# amp_ganho_ajustavel.net
KiCad netlist of a schematic drawn in Altium Designer
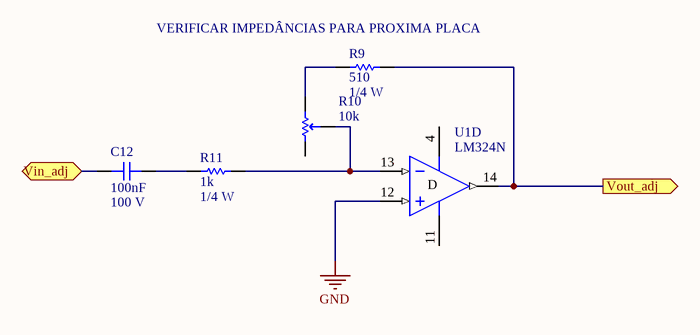
[diagram p0: amp_ganho_ajustavel.SchDoc]

(export (version "E")
  (design (tool "Eeschema 10.0.6"))
  (components
    (comp (ref "C12")
      (value "100nF")
      (footprint "0805C")
      (description "Capacitor")
      (fields (field (name "VOLTAGE") "100 V") (field (name "PUBLISHER") "Altium Limited"))
      (libsource (lib "GPDSE") (part "Capacitor"))
    )
    (comp (ref "R9")
      (value "510")
      (footprint "0805R")
      (description "Resistor")
      (fields
        (field (name "TOLERANCE") "5%")
        (field (name "POWER") "1/4 W")
        (field (name "PUBLISHER") "Altium Limited")
      )
      (libsource (lib "GPDSE") (part "Resistor"))
    )
    (comp (ref "R10")
      (value "10k")
      (footprint "Trimpot-3296W")
      (description "Trimpot")
      (libsource (lib "GPDSE") (part "Trimpot"))
    )
    (comp (ref "R11")
      (value "1k")
      (footprint "0805R")
      (description "Resistor")
      (fields
        (field (name "TOLERANCE") "5%")
        (field (name "POWER") "1/4 W")
        (field (name "PUBLISHER") "Altium Limited")
      )
      (libsource (lib "GPDSE") (part "Resistor"))
    )
    (comp (ref "U1")
      (value "LM324N")
      (footprint "N014")
      (description "Quadruple Operational Amplifier")
      (fields (field (name "PUBLISHER") "Altium Limited"))
      (libsource (lib "TI Operational Amplifier") (part "LM324N"))
    )
  )
  (nets
    (net (code "1") (name "/Vin_adj") (class "Default")
      (node (ref "C12") (pin "1") (pinfunction "1_1") (pintype "passive"))
    )
    (net (code "2") (name "/Vout_adj") (class "Default")
      (node (ref "R9") (pin "2") (pinfunction "2_2") (pintype "passive"))
      (node (ref "U1") (pin "14") (pinfunction "OUT_14") (pintype "output"))
    )
    (net (code "3") (name "GND") (class "Default")
      (node (ref "U1") (pin "12") (pinfunction "IN+_12") (pintype "input"))
    )
    (net (code "4") (name "Net-(C12-Pad2)") (class "Default")
      (node (ref "C12") (pin "2") (pinfunction "2_2") (pintype "passive"))
      (node (ref "R11") (pin "1") (pinfunction "1_1") (pintype "passive"))
    )
    (net (code "5") (name "Net-(R10-Pad1)") (class "Default")
      (node (ref "R10") (pin "1") (pinfunction "1_1") (pintype "passive"))
      (node (ref "R9") (pin "1") (pinfunction "1_1") (pintype "passive"))
    )
    (net (code "6") (name "Net-(U1D-IN-)") (class "Default")
      (node (ref "R10") (pin "3") (pinfunction "3_3") (pintype "passive"))
      (node (ref "R11") (pin "2") (pinfunction "2_2") (pintype "passive"))
      (node (ref "U1") (pin "13") (pinfunction "IN-_13") (pintype "input"))
    )
    (net (code "7") (name "unconnected-(R10-Pad2)") (class "Default")
      (node (ref "R10") (pin "2") (pinfunction "2_2") (pintype "passive"))
    )
    (net (code "8") (name "unconnected-(U1D-V+-Pad4)") (class "Default")
      (node (ref "U1") (pin "4") (pinfunction "V+_4") (pintype "power_in"))
    )
    (net (code "9") (name "unconnected-(U1D-V--Pad11)") (class "Default")
      (node (ref "U1") (pin "11") (pinfunction "V-_11") (pintype "power_in"))
    )
  )
)
